# QCopterRC_POWER_Sch.net
KiCad netlist of a schematic drawn in Altium Designer
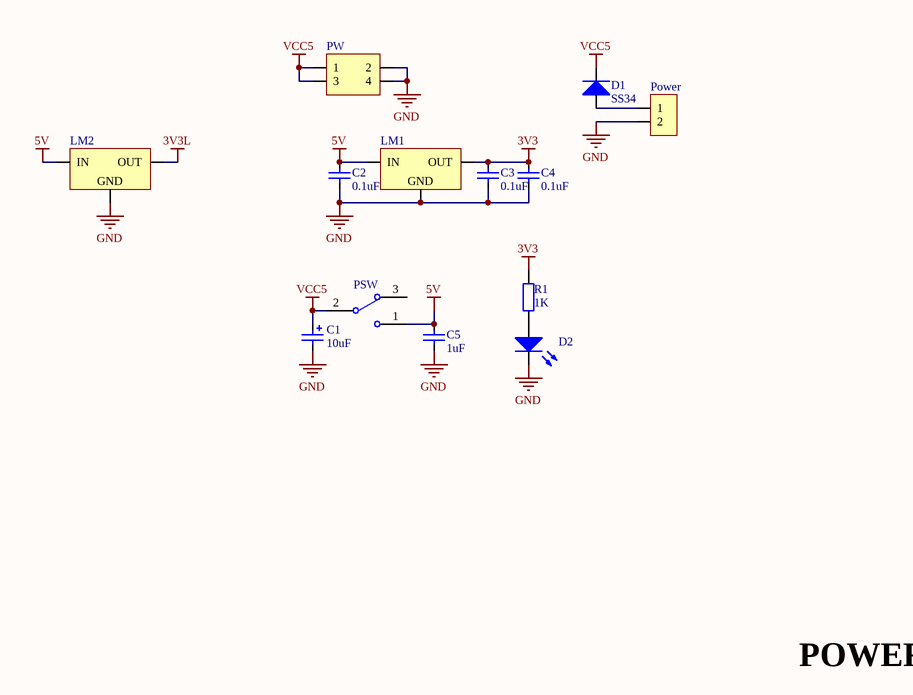
[diagram p0: QCopterRC_POWER_Sch.SchDoc]

(export (version "E")
  (design (tool "Eeschema 10.0.6"))
  (components
    (comp (ref "C1")
      (value "10uF")
      (footprint "PCB_Passive:CAP_TAN_B1210")
      (description "Capacitor")
      (fields (field (name "Comment") "Cap_Tan_1210"))
      (libsource (lib "SCH_Passive") (part "Cap_Tan_1210"))
    )
    (comp (ref "C2")
      (value "0.1uF")
      (footprint "PCB_Passive:CAP_0603")
      (description "Capacitor")
      (fields (field (name "Comment") "Cap_0603"))
      (libsource (lib "SCH_Passive") (part "Cap_0603"))
    )
    (comp (ref "C3")
      (value "0.1uF")
      (footprint "PCB_Passive:CAP_0603")
      (description "Capacitor")
      (fields (field (name "Comment") "Cap_0603"))
      (libsource (lib "SCH_Passive") (part "Cap_0603"))
    )
    (comp (ref "C4")
      (value "0.1uF")
      (footprint "PCB_Passive:CAP_0603")
      (description "Capacitor")
      (fields (field (name "Comment") "Cap_0603"))
      (libsource (lib "SCH_Passive") (part "Cap_0603"))
    )
    (comp (ref "C5")
      (value "1uF")
      (footprint "PCB_Passive:CAP_0603")
      (description "Capacitor")
      (fields (field (name "Comment") "Cap_0603"))
      (libsource (lib "SCH_Passive") (part "Cap_0603"))
    )
    (comp (ref "D1")
      (value "Diode_SMA")
      (footprint "PCB_Active:DO-214AC")
      (description "Diode")
      (fields (field (name "SMA") "SS34"))
      (libsource (lib "SCH_Active") (part "Diode_SMA"))
    )
    (comp (ref "D2")
      (value "LED_0603_WHITE")
      (footprint "PCB_Active:LED_0603_WHITE")
      (description "LED")
      (libsource (lib "SCH_Active") (part "LED_0603_WHITE"))
    )
    (comp (ref "LM1")
      (value "LM1117")
      (footprint "PCB_IC:SOT223")
      (description "Power")
      (libsource (lib "SCH_IC") (part "LM1117"))
    )
    (comp (ref "LM2")
      (value "LM1117")
      (footprint "PCB_IC:SOT223")
      (description "Power")
      (libsource (lib "SCH_IC") (part "LM1117"))
    )
    (comp (ref "Power")
      (value "HDR1X2_90_2.54")
      (footprint "PCB_Connector:HDR1X2_90_2.54")
      (description "Header")
      (libsource (lib "SCH_Connector") (part "HDR1X2_90_2.54"))
    )
    (comp (ref "PSW")
      (value "SW_SPDT_4.3X8.6_D90")
      (footprint "PCB_Switch:SW_SPDT_4.3X8.6_D90")
      (description "Switch")
      (libsource (lib "SCH_Switch") (part "SW_SPDT_4.3X8.6_D90"))
    )
    (comp (ref "PW")
      (value "HDR2X2_90_2.54")
      (footprint "PCB_Connector:HDR2X2_90_2.54")
      (description "Header")
      (libsource (lib "SCH_Connector") (part "HDR2X2_90_2.54"))
    )
    (comp (ref "R1")
      (value "1K")
      (footprint "PCB_Passive:RES_0603")
      (description "Resistor")
      (fields (field (name "Comment") "Res_0603"))
      (libsource (lib "SCH_Passive") (part "Res_0603"))
    )
  )
  (nets
    (net (code "1") (name "3V3") (class "Default")
      (node (ref "C3") (pin "2") (pinfunction "2_2") (pintype "passive"))
      (node (ref "C4") (pin "2") (pinfunction "2_2") (pintype "passive"))
      (node (ref "LM1") (pin "2") (pinfunction "OUT_2") (pintype "power_in"))
      (node (ref "R1") (pin "2") (pinfunction "2_2") (pintype "passive"))
    )
    (net (code "2") (name "3V3L") (class "Default")
      (node (ref "LM2") (pin "2") (pinfunction "OUT_2") (pintype "power_in"))
    )
    (net (code "3") (name "5V") (class "Default")
      (node (ref "C2") (pin "1") (pinfunction "1_1") (pintype "passive"))
      (node (ref "C5") (pin "2") (pinfunction "2_2") (pintype "passive"))
      (node (ref "LM1") (pin "3") (pinfunction "IN_3") (pintype "power_in"))
      (node (ref "LM2") (pin "3") (pinfunction "IN_3") (pintype "power_in"))
      (node (ref "PSW") (pin "1") (pinfunction "1_1") (pintype "passive"))
    )
    (net (code "4") (name "GND") (class "Default")
      (node (ref "C1") (pin "2") (pinfunction "2_2") (pintype "passive"))
      (node (ref "C2") (pin "2") (pinfunction "2_2") (pintype "passive"))
      (node (ref "C3") (pin "1") (pinfunction "1_1") (pintype "passive"))
      (node (ref "C4") (pin "1") (pinfunction "1_1") (pintype "passive"))
      (node (ref "C5") (pin "1") (pinfunction "1_1") (pintype "passive"))
      (node (ref "D2") (pin "2") (pinfunction "K_2") (pintype "passive"))
      (node (ref "LM1") (pin "1") (pinfunction "GND_1") (pintype "power_in"))
      (node (ref "LM2") (pin "1") (pinfunction "GND_1") (pintype "power_in"))
      (node (ref "PW") (pin "2") (pinfunction "2_2") (pintype "passive"))
      (node (ref "PW") (pin "4") (pinfunction "4_4") (pintype "passive"))
      (node (ref "Power") (pin "2") (pinfunction "2_2") (pintype "passive"))
    )
    (net (code "5") (name "Net-(D1-A)") (class "Default")
      (node (ref "D1") (pin "1") (pinfunction "A_1") (pintype "passive"))
      (node (ref "Power") (pin "1") (pinfunction "1_1") (pintype "passive"))
    )
    (net (code "6") (name "Net-(D2-A)") (class "Default")
      (node (ref "D2") (pin "1") (pinfunction "A_1") (pintype "passive"))
      (node (ref "R1") (pin "1") (pinfunction "1_1") (pintype "passive"))
    )
    (net (code "7") (name "VCC5") (class "Default")
      (node (ref "C1") (pin "1") (pinfunction "1_1") (pintype "passive"))
      (node (ref "D1") (pin "2") (pinfunction "K_2") (pintype "passive"))
      (node (ref "PSW") (pin "2") (pinfunction "2_2") (pintype "passive"))
      (node (ref "PW") (pin "1") (pinfunction "1_1") (pintype "passive"))
      (node (ref "PW") (pin "3") (pinfunction "3_3") (pintype "passive"))
    )
    (net (code "8") (name "unconnected-(PSW-Pad3)") (class "Default")
      (node (ref "PSW") (pin "3") (pinfunction "3_3") (pintype "passive"))
    )
  )
)
